# 117_01_TIMER_GATE.net
KiCad netlist of a schematic drawn in EAGLE
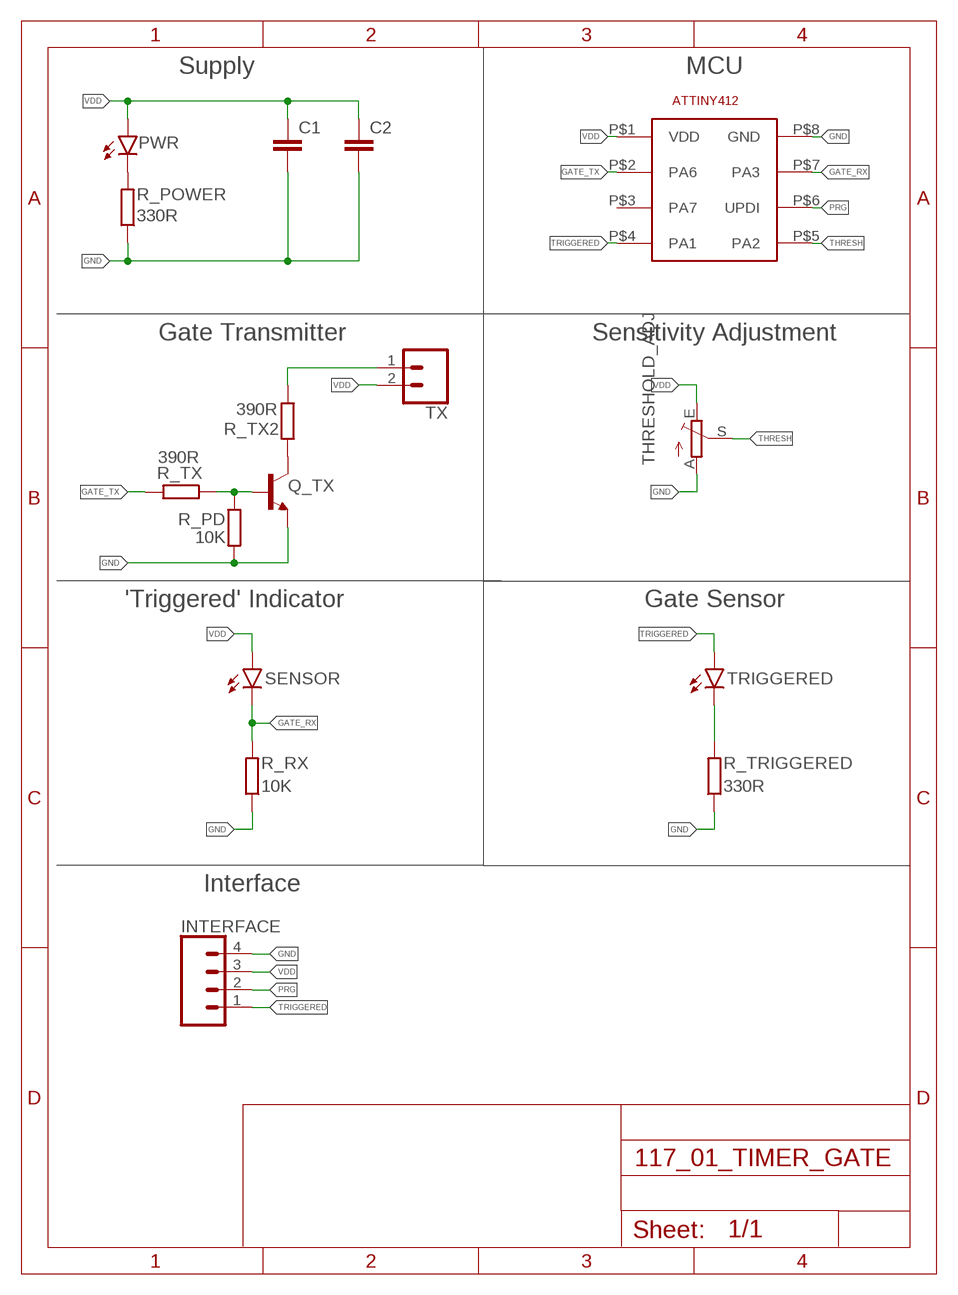
[diagram p0: schematic, sheet 1]

(export (version "E")
  (design (tool "Eeschema 10.0.6"))
  (components
    (comp (ref "C1")
      (value "C-EUC0805K")
      (footprint "eagle-import:C0805K")
      (libsource (lib "eagle-import") (part "C-EUC0805K"))
    )
    (comp (ref "C2")
      (value "C-EUC0805K")
      (footprint "eagle-import:C0805K")
      (libsource (lib "eagle-import") (part "C-EUC0805K"))
    )
    (comp (ref "INTERFACE")
      (value "CONN_04LONGPADS")
      (footprint "eagle-import:1X04_LONGPADS")
      (libsource (lib "eagle-import") (part "CONN_04LONGPADS"))
    )
    (comp (ref "PWR")
      (value "LEDSML0805")
      (footprint "eagle-import:SML0805")
      (libsource (lib "eagle-import") (part "LEDSML0805"))
    )
    (comp (ref "Q_TX")
      (value "2N2222-NPN-TO92-EBC")
      (footprint "eagle-import:TO92-EBC")
      (libsource (lib "eagle-import") (part "-NPN-TO92-EBC2N2222"))
    )
    (comp (ref "R_PD")
      (value "10K")
      (footprint "eagle-import:M0805")
      (libsource (lib "eagle-import") (part "R-EU_M0805"))
    )
    (comp (ref "R_POWER")
      (value "330R")
      (footprint "eagle-import:M0805")
      (libsource (lib "eagle-import") (part "R-EU_M0805"))
    )
    (comp (ref "R_RX")
      (value "10K")
      (footprint "eagle-import:M0805")
      (libsource (lib "eagle-import") (part "R-EU_M0805"))
    )
    (comp (ref "R_TRIGGERED")
      (value "330R")
      (footprint "eagle-import:M0805")
      (libsource (lib "eagle-import") (part "R-EU_M0805"))
    )
    (comp (ref "R_TX")
      (value "390R")
      (footprint "eagle-import:M0805")
      (libsource (lib "eagle-import") (part "R-EU_M0805"))
    )
    (comp (ref "R_TX2")
      (value "390R")
      (footprint "eagle-import:M0805")
      (libsource (lib "eagle-import") (part "R-EU_M0805"))
    )
    (comp (ref "SENSOR")
      (value "LED5MM")
      (footprint "eagle-import:LED_5MM")
      (libsource (lib "eagle-import") (part "LED5MM"))
    )
    (comp (ref "THRESHOLD_ADJ")
      (value "TRIM_EU-S64W")
      (footprint "eagle-import:S64W")
      (libsource (lib "eagle-import") (part "TRIM_EU-S64W"))
    )
    (comp (ref "TRIGGERED")
      (value "LED5MM")
      (footprint "eagle-import:LED_5MM")
      (libsource (lib "eagle-import") (part "LED5MM"))
    )
    (comp (ref "TX")
      (value "CONN_02PTH3")
      (footprint "eagle-import:1X02_LONGPADS")
      (libsource (lib "eagle-import") (part "CONN_02PTH3"))
    )
    (comp (ref "U$1")
      (value "ATTINY412")
      (footprint "eagle-import:ATTINY412")
      (libsource (lib "eagle-import") (part "ATTINY412"))
    )
  )
  (nets
    (net (code "1") (name "GATE_RX") (class "Default")
      (node (ref "R_RX") (pin "2") (pinfunction "2_2") (pintype "passive"))
      (node (ref "SENSOR") (pin "K") (pinfunction "C_K") (pintype "passive"))
      (node (ref "U$1") (pin "P$7") (pinfunction "PA3_P$7") (pintype "bidirectional"))
    )
    (net (code "2") (name "GATE_TX") (class "Default")
      (node (ref "R_TX") (pin "2") (pinfunction "2_2") (pintype "passive"))
      (node (ref "U$1") (pin "P$2") (pinfunction "PA6_P$2") (pintype "bidirectional"))
    )
    (net (code "3") (name "GND") (class "Default")
      (node (ref "C1") (pin "2") (pinfunction "2_2") (pintype "passive"))
      (node (ref "C2") (pin "2") (pinfunction "2_2") (pintype "passive"))
      (node (ref "INTERFACE") (pin "4") (pinfunction "4_4") (pintype "passive"))
      (node (ref "Q_TX") (pin "E") (pinfunction "E_E") (pintype "passive"))
      (node (ref "R_PD") (pin "2") (pinfunction "2_2") (pintype "passive"))
      (node (ref "R_POWER") (pin "1") (pinfunction "1_1") (pintype "passive"))
      (node (ref "R_RX") (pin "1") (pinfunction "1_1") (pintype "passive"))
      (node (ref "R_TRIGGERED") (pin "1") (pinfunction "1_1") (pintype "passive"))
      (node (ref "THRESHOLD_ADJ") (pin "A") (pinfunction "A_A") (pintype "passive"))
      (node (ref "U$1") (pin "P$8") (pinfunction "GND_P$8") (pintype "bidirectional"))
    )
    (net (code "4") (name "Net-(PWR-PadC)") (class "Default")
      (node (ref "PWR") (pin "C") (pinfunction "C_C") (pintype "passive"))
      (node (ref "R_POWER") (pin "2") (pinfunction "2_2") (pintype "passive"))
    )
    (net (code "5") (name "Net-(Q_TX-PadB)") (class "Default")
      (node (ref "Q_TX") (pin "B") (pinfunction "B_B") (pintype "passive"))
      (node (ref "R_PD") (pin "1") (pinfunction "1_1") (pintype "passive"))
      (node (ref "R_TX") (pin "1") (pinfunction "1_1") (pintype "passive"))
    )
    (net (code "6") (name "Net-(Q_TX-PadC)") (class "Default")
      (node (ref "Q_TX") (pin "C") (pinfunction "C_C") (pintype "passive"))
      (node (ref "R_TX2") (pin "2") (pinfunction "2_2") (pintype "passive"))
    )
    (net (code "7") (name "Net-(R_TX2-Pad1)") (class "Default")
      (node (ref "R_TX2") (pin "1") (pinfunction "1_1") (pintype "passive"))
      (node (ref "TX") (pin "1") (pinfunction "1_1") (pintype "passive"))
    )
    (net (code "8") (name "Net-(TRIGGERED-C)") (class "Default")
      (node (ref "R_TRIGGERED") (pin "2") (pinfunction "2_2") (pintype "passive"))
      (node (ref "TRIGGERED") (pin "K") (pinfunction "C_K") (pintype "passive"))
    )
    (net (code "9") (name "PRG") (class "Default")
      (node (ref "INTERFACE") (pin "2") (pinfunction "2_2") (pintype "passive"))
      (node (ref "U$1") (pin "P$6") (pinfunction "UPDI_P$6") (pintype "bidirectional"))
    )
    (net (code "10") (name "THRESH") (class "Default")
      (node (ref "THRESHOLD_ADJ") (pin "S") (pinfunction "S_S") (pintype "passive"))
      (node (ref "U$1") (pin "P$5") (pinfunction "PA2_P$5") (pintype "bidirectional"))
    )
    (net (code "11") (name "TRIGGERED") (class "Default")
      (node (ref "INTERFACE") (pin "1") (pinfunction "1_1") (pintype "passive"))
      (node (ref "TRIGGERED") (pin "A") (pinfunction "A_A") (pintype "passive"))
      (node (ref "U$1") (pin "P$4") (pinfunction "PA1_P$4") (pintype "bidirectional"))
    )
    (net (code "12") (name "VDD") (class "Default")
      (node (ref "C1") (pin "1") (pinfunction "1_1") (pintype "passive"))
      (node (ref "C2") (pin "1") (pinfunction "1_1") (pintype "passive"))
      (node (ref "INTERFACE") (pin "3") (pinfunction "3_3") (pintype "passive"))
      (node (ref "PWR") (pin "A") (pinfunction "A_A") (pintype "passive"))
      (node (ref "SENSOR") (pin "A") (pinfunction "A_A") (pintype "passive"))
      (node (ref "THRESHOLD_ADJ") (pin "E") (pinfunction "E_E") (pintype "passive"))
      (node (ref "TX") (pin "2") (pinfunction "2_2") (pintype "passive"))
      (node (ref "U$1") (pin "P$1") (pinfunction "VDD_P$1") (pintype "bidirectional"))
    )
    (net (code "13") (name "unconnected-(U$1-PA7-PadP$3)") (class "Default")
      (node (ref "U$1") (pin "P$3") (pinfunction "PA7_P$3") (pintype "bidirectional"))
    )
  )
)
